# amp.net
KiCad netlist of a schematic drawn in EAGLE
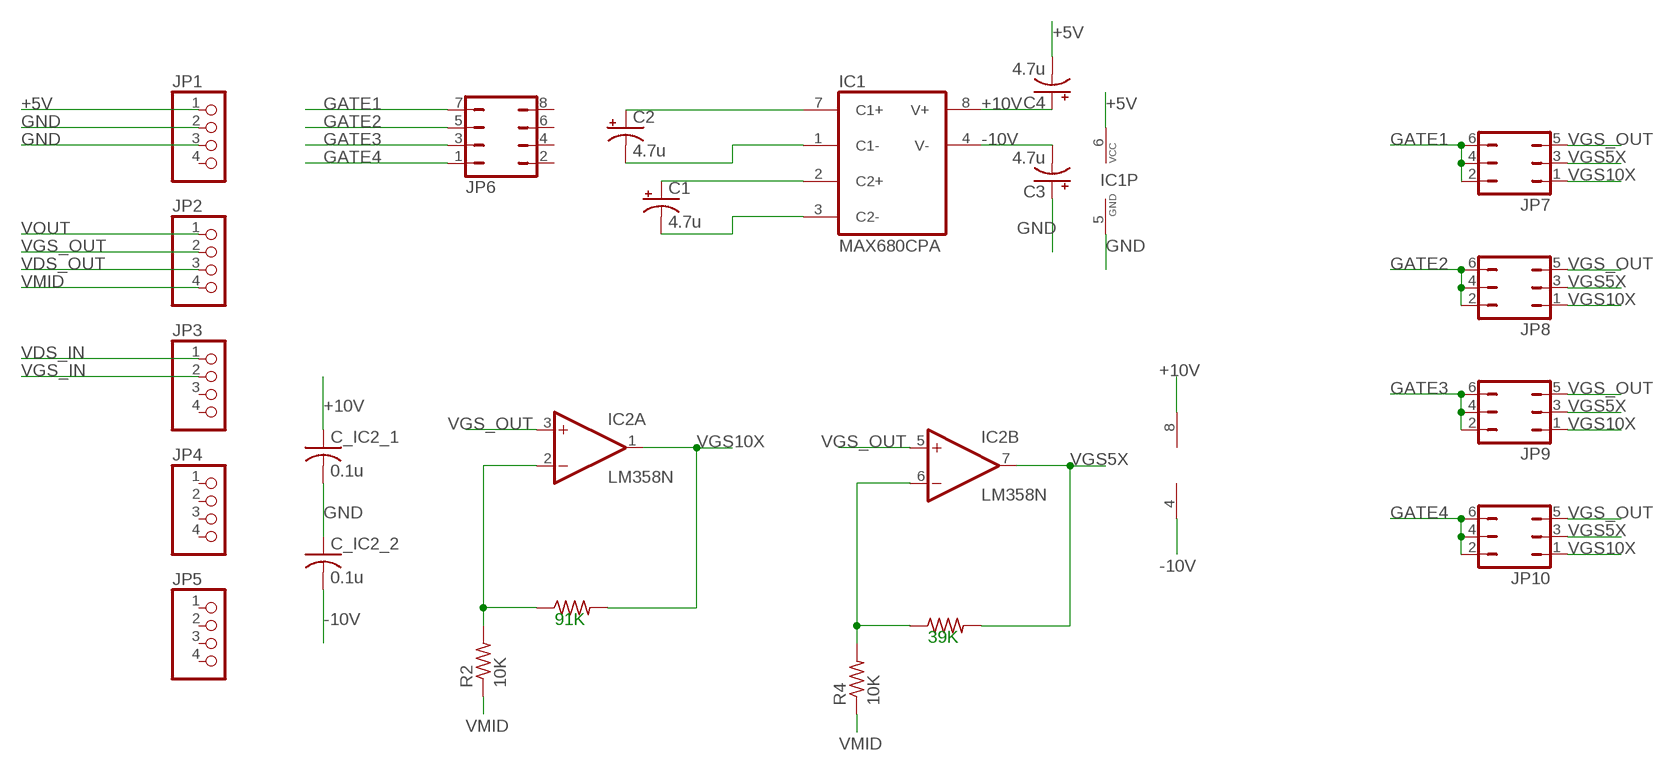
[diagram p0: schematic, sheet 1]

(export (version "E")
  (design (tool "Eeschema 10.0.6"))
  (components
    (comp (ref "C1")
      (value "4.7u")
      (footprint "eagle-import:B45181B")
      (libsource (lib "eagle-import") (part "CPOL-USB45181B"))
    )
    (comp (ref "C2")
      (value "4.7u")
      (footprint "eagle-import:B45181B")
      (libsource (lib "eagle-import") (part "CPOL-USB45181B"))
    )
    (comp (ref "C3")
      (value "4.7u")
      (footprint "eagle-import:B45181B")
      (libsource (lib "eagle-import") (part "CPOL-USB45181B"))
    )
    (comp (ref "C4")
      (value "4.7u")
      (footprint "eagle-import:B45181B")
      (libsource (lib "eagle-import") (part "CPOL-USB45181B"))
    )
    (comp (ref "C_IC2_1")
      (value "0.1u")
      (footprint "eagle-import:C025-024X044")
      (libsource (lib "eagle-import") (part "C-US025-024X044"))
    )
    (comp (ref "C_IC2_2")
      (value "0.1u")
      (footprint "eagle-import:C025-024X044")
      (libsource (lib "eagle-import") (part "C-US025-024X044"))
    )
    (comp (ref "IC1")
      (value "MAX680CPA")
      (footprint "eagle-import:DIL08")
      (libsource (lib "eagle-import") (part "MAX680CPA"))
    )
    (comp (ref "IC2")
      (value "LM358N")
      (footprint "eagle-import:DIL08")
      (libsource (lib "eagle-import") (part "LM358N"))
    )
    (comp (ref "JP1")
      (value "PINHD-1X4")
      (footprint "eagle-import:1X04")
      (libsource (lib "eagle-import") (part "PINHD-1X4"))
    )
    (comp (ref "JP2")
      (value "PINHD-1X4")
      (footprint "eagle-import:1X04")
      (libsource (lib "eagle-import") (part "PINHD-1X4"))
    )
    (comp (ref "JP3")
      (value "PINHD-1X4")
      (footprint "eagle-import:1X04")
      (libsource (lib "eagle-import") (part "PINHD-1X4"))
    )
    (comp (ref "JP4")
      (value "PINHD-1X4")
      (footprint "eagle-import:1X04")
      (libsource (lib "eagle-import") (part "PINHD-1X4"))
    )
    (comp (ref "JP5")
      (value "PINHD-1X4")
      (footprint "eagle-import:1X04")
      (libsource (lib "eagle-import") (part "PINHD-1X4"))
    )
    (comp (ref "JP6")
      (value "JP4Q")
      (footprint "eagle-import:JP4Q")
      (libsource (lib "eagle-import") (part "JP4Q"))
    )
    (comp (ref "JP7")
      (value "JP3Q")
      (footprint "eagle-import:JP3Q")
      (libsource (lib "eagle-import") (part "JP3Q"))
    )
    (comp (ref "JP8")
      (value "JP3Q")
      (footprint "eagle-import:JP3Q")
      (libsource (lib "eagle-import") (part "JP3Q"))
    )
    (comp (ref "JP9")
      (value "JP3Q")
      (footprint "eagle-import:JP3Q")
      (libsource (lib "eagle-import") (part "JP3Q"))
    )
    (comp (ref "JP10")
      (value "JP3Q")
      (footprint "eagle-import:JP3Q")
      (libsource (lib "eagle-import") (part "JP3Q"))
    )
    (comp (ref "R1")
      (value "91K")
      (footprint "eagle-import:0204_7")
      (libsource (lib "eagle-import") (part "R-US_0204/7"))
    )
    (comp (ref "R2")
      (value "10K")
      (footprint "eagle-import:0204_7")
      (libsource (lib "eagle-import") (part "R-US_0204/7"))
    )
    (comp (ref "R3")
      (value "39K")
      (footprint "eagle-import:0204_7")
      (libsource (lib "eagle-import") (part "R-US_0204/7"))
    )
    (comp (ref "R4")
      (value "10K")
      (footprint "eagle-import:0204_7")
      (libsource (lib "eagle-import") (part "R-US_0204/7"))
    )
  )
  (nets
    (net (code "1") (name "/+5V") (class "Default")
      (node (ref "C4") (pin "-") (pinfunction "-_-") (pintype "passive"))
      (node (ref "IC1") (pin "6") (pinfunction "VCC_6") (pintype "power_in"))
      (node (ref "JP1") (pin "1") (pinfunction "1_1") (pintype "passive"))
    )
    (net (code "2") (name "/+10V") (class "Default")
      (node (ref "C4") (pin "+") (pinfunction "+_+") (pintype "passive"))
      (node (ref "C_IC2_1") (pin "1") (pinfunction "1_1") (pintype "passive"))
      (node (ref "IC1") (pin "8") (pinfunction "V+_8") (pintype "output"))
      (node (ref "IC2") (pin "8") (pinfunction "V+_8") (pintype "power_in"))
    )
    (net (code "3") (name "/-10V") (class "Default")
      (node (ref "C3") (pin "-") (pinfunction "-_-") (pintype "passive"))
      (node (ref "C_IC2_2") (pin "2") (pinfunction "2_2") (pintype "passive"))
      (node (ref "IC1") (pin "4") (pinfunction "V-_4") (pintype "output"))
      (node (ref "IC2") (pin "4") (pinfunction "V-_4") (pintype "power_in"))
    )
    (net (code "4") (name "/GATE1") (class "Default")
      (node (ref "JP6") (pin "7") (pinfunction "7_7") (pintype "passive"))
      (node (ref "JP7") (pin "2") (pinfunction "2_2") (pintype "passive"))
      (node (ref "JP7") (pin "4") (pinfunction "4_4") (pintype "passive"))
      (node (ref "JP7") (pin "6") (pinfunction "6_6") (pintype "passive"))
    )
    (net (code "5") (name "/GATE2") (class "Default")
      (node (ref "JP6") (pin "5") (pinfunction "5_5") (pintype "passive"))
      (node (ref "JP8") (pin "2") (pinfunction "2_2") (pintype "passive"))
      (node (ref "JP8") (pin "4") (pinfunction "4_4") (pintype "passive"))
      (node (ref "JP8") (pin "6") (pinfunction "6_6") (pintype "passive"))
    )
    (net (code "6") (name "/GATE3") (class "Default")
      (node (ref "JP6") (pin "3") (pinfunction "3_3") (pintype "passive"))
      (node (ref "JP9") (pin "2") (pinfunction "2_2") (pintype "passive"))
      (node (ref "JP9") (pin "4") (pinfunction "4_4") (pintype "passive"))
      (node (ref "JP9") (pin "6") (pinfunction "6_6") (pintype "passive"))
    )
    (net (code "7") (name "/GATE4") (class "Default")
      (node (ref "JP10") (pin "2") (pinfunction "2_2") (pintype "passive"))
      (node (ref "JP10") (pin "4") (pinfunction "4_4") (pintype "passive"))
      (node (ref "JP10") (pin "6") (pinfunction "6_6") (pintype "passive"))
      (node (ref "JP6") (pin "1") (pinfunction "1_1") (pintype "passive"))
    )
    (net (code "8") (name "/GND") (class "Default")
      (node (ref "C3") (pin "+") (pinfunction "+_+") (pintype "passive"))
      (node (ref "C_IC2_1") (pin "2") (pinfunction "2_2") (pintype "passive"))
      (node (ref "C_IC2_2") (pin "1") (pinfunction "1_1") (pintype "passive"))
      (node (ref "IC1") (pin "5") (pinfunction "GND_5") (pintype "power_in"))
      (node (ref "JP1") (pin "2") (pinfunction "2_2") (pintype "passive"))
      (node (ref "JP1") (pin "3") (pinfunction "3_3") (pintype "passive"))
    )
    (net (code "9") (name "/VDS_IN") (class "Default")
      (node (ref "JP3") (pin "1") (pinfunction "1_1") (pintype "passive"))
    )
    (net (code "10") (name "/VDS_OUT") (class "Default")
      (node (ref "JP2") (pin "3") (pinfunction "3_3") (pintype "passive"))
    )
    (net (code "11") (name "/VGS5X") (class "Default")
      (node (ref "IC2") (pin "7") (pinfunction "OUT_7") (pintype "output"))
      (node (ref "JP10") (pin "3") (pinfunction "3_3") (pintype "passive"))
      (node (ref "JP7") (pin "3") (pinfunction "3_3") (pintype "passive"))
      (node (ref "JP8") (pin "3") (pinfunction "3_3") (pintype "passive"))
      (node (ref "JP9") (pin "3") (pinfunction "3_3") (pintype "passive"))
      (node (ref "R3") (pin "2") (pinfunction "2_2") (pintype "passive"))
    )
    (net (code "12") (name "/VGS10X") (class "Default")
      (node (ref "IC2") (pin "1") (pinfunction "OUT_1") (pintype "output"))
      (node (ref "JP10") (pin "1") (pinfunction "1_1") (pintype "passive"))
      (node (ref "JP7") (pin "1") (pinfunction "1_1") (pintype "passive"))
      (node (ref "JP8") (pin "1") (pinfunction "1_1") (pintype "passive"))
      (node (ref "JP9") (pin "1") (pinfunction "1_1") (pintype "passive"))
      (node (ref "R1") (pin "2") (pinfunction "2_2") (pintype "passive"))
    )
    (net (code "13") (name "/VGS_IN") (class "Default")
      (node (ref "JP3") (pin "2") (pinfunction "2_2") (pintype "passive"))
    )
    (net (code "14") (name "/VGS_OUT") (class "Default")
      (node (ref "IC2") (pin "3") (pinfunction "+IN_3") (pintype "input"))
      (node (ref "IC2") (pin "5") (pinfunction "+IN_5") (pintype "input"))
      (node (ref "JP10") (pin "5") (pinfunction "5_5") (pintype "passive"))
      (node (ref "JP2") (pin "2") (pinfunction "2_2") (pintype "passive"))
      (node (ref "JP7") (pin "5") (pinfunction "5_5") (pintype "passive"))
      (node (ref "JP8") (pin "5") (pinfunction "5_5") (pintype "passive"))
      (node (ref "JP9") (pin "5") (pinfunction "5_5") (pintype "passive"))
    )
    (net (code "15") (name "/VMID") (class "Default")
      (node (ref "JP2") (pin "4") (pinfunction "4_4") (pintype "passive"))
      (node (ref "R2") (pin "1") (pinfunction "1_1") (pintype "passive"))
      (node (ref "R4") (pin "1") (pinfunction "1_1") (pintype "passive"))
    )
    (net (code "16") (name "/VOUT") (class "Default")
      (node (ref "JP2") (pin "1") (pinfunction "1_1") (pintype "passive"))
    )
    (net (code "17") (name "Net-(IC1A-C1+)") (class "Default")
      (node (ref "C2") (pin "+") (pinfunction "+_+") (pintype "passive"))
      (node (ref "IC1") (pin "7") (pinfunction "C1+_7") (pintype "passive"))
    )
    (net (code "18") (name "Net-(IC1A-C1-)") (class "Default")
      (node (ref "C2") (pin "-") (pinfunction "-_-") (pintype "passive"))
      (node (ref "IC1") (pin "1") (pinfunction "C1-_1") (pintype "passive"))
    )
    (net (code "19") (name "Net-(IC1A-C2+)") (class "Default")
      (node (ref "C1") (pin "+") (pinfunction "+_+") (pintype "passive"))
      (node (ref "IC1") (pin "2") (pinfunction "C2+_2") (pintype "passive"))
    )
    (net (code "20") (name "Net-(IC1A-C2-)") (class "Default")
      (node (ref "C1") (pin "-") (pinfunction "-_-") (pintype "passive"))
      (node (ref "IC1") (pin "3") (pinfunction "C2-_3") (pintype "passive"))
    )
    (net (code "21") (name "Net-(IC2A--IN)") (class "Default")
      (node (ref "IC2") (pin "2") (pinfunction "-IN_2") (pintype "input"))
      (node (ref "R1") (pin "1") (pinfunction "1_1") (pintype "passive"))
      (node (ref "R2") (pin "2") (pinfunction "2_2") (pintype "passive"))
    )
    (net (code "22") (name "Net-(IC2B--IN)") (class "Default")
      (node (ref "IC2") (pin "6") (pinfunction "-IN_6") (pintype "input"))
      (node (ref "R3") (pin "1") (pinfunction "1_1") (pintype "passive"))
      (node (ref "R4") (pin "2") (pinfunction "2_2") (pintype "passive"))
    )
    (net (code "23") (name "unconnected-(JP1-Pad4)") (class "Default")
      (node (ref "JP1") (pin "4") (pinfunction "4_4") (pintype "passive"))
    )
    (net (code "24") (name "unconnected-(JP3-Pad3)") (class "Default")
      (node (ref "JP3") (pin "3") (pinfunction "3_3") (pintype "passive"))
    )
    (net (code "25") (name "unconnected-(JP3-Pad4)") (class "Default")
      (node (ref "JP3") (pin "4") (pinfunction "4_4") (pintype "passive"))
    )
    (net (code "26") (name "unconnected-(JP4-Pad1)") (class "Default")
      (node (ref "JP4") (pin "1") (pinfunction "1_1") (pintype "passive"))
    )
    (net (code "27") (name "unconnected-(JP4-Pad2)") (class "Default")
      (node (ref "JP4") (pin "2") (pinfunction "2_2") (pintype "passive"))
    )
    (net (code "28") (name "unconnected-(JP4-Pad3)") (class "Default")
      (node (ref "JP4") (pin "3") (pinfunction "3_3") (pintype "passive"))
    )
    (net (code "29") (name "unconnected-(JP4-Pad4)") (class "Default")
      (node (ref "JP4") (pin "4") (pinfunction "4_4") (pintype "passive"))
    )
    (net (code "30") (name "unconnected-(JP5-Pad1)") (class "Default")
      (node (ref "JP5") (pin "1") (pinfunction "1_1") (pintype "passive"))
    )
    (net (code "31") (name "unconnected-(JP5-Pad2)") (class "Default")
      (node (ref "JP5") (pin "2") (pinfunction "2_2") (pintype "passive"))
    )
    (net (code "32") (name "unconnected-(JP5-Pad3)") (class "Default")
      (node (ref "JP5") (pin "3") (pinfunction "3_3") (pintype "passive"))
    )
    (net (code "33") (name "unconnected-(JP5-Pad4)") (class "Default")
      (node (ref "JP5") (pin "4") (pinfunction "4_4") (pintype "passive"))
    )
    (net (code "34") (name "unconnected-(JP6-Pad2)") (class "Default")
      (node (ref "JP6") (pin "2") (pinfunction "2_2") (pintype "passive"))
    )
    (net (code "35") (name "unconnected-(JP6-Pad4)") (class "Default")
      (node (ref "JP6") (pin "4") (pinfunction "4_4") (pintype "passive"))
    )
    (net (code "36") (name "unconnected-(JP6-Pad6)") (class "Default")
      (node (ref "JP6") (pin "6") (pinfunction "6_6") (pintype "passive"))
    )
    (net (code "37") (name "unconnected-(JP6-Pad8)") (class "Default")
      (node (ref "JP6") (pin "8") (pinfunction "8_8") (pintype "passive"))
    )
  )
)
